# LOTP_ESP32_MCU_V3.net
KiCad netlist of a schematic drawn in EasyEDA
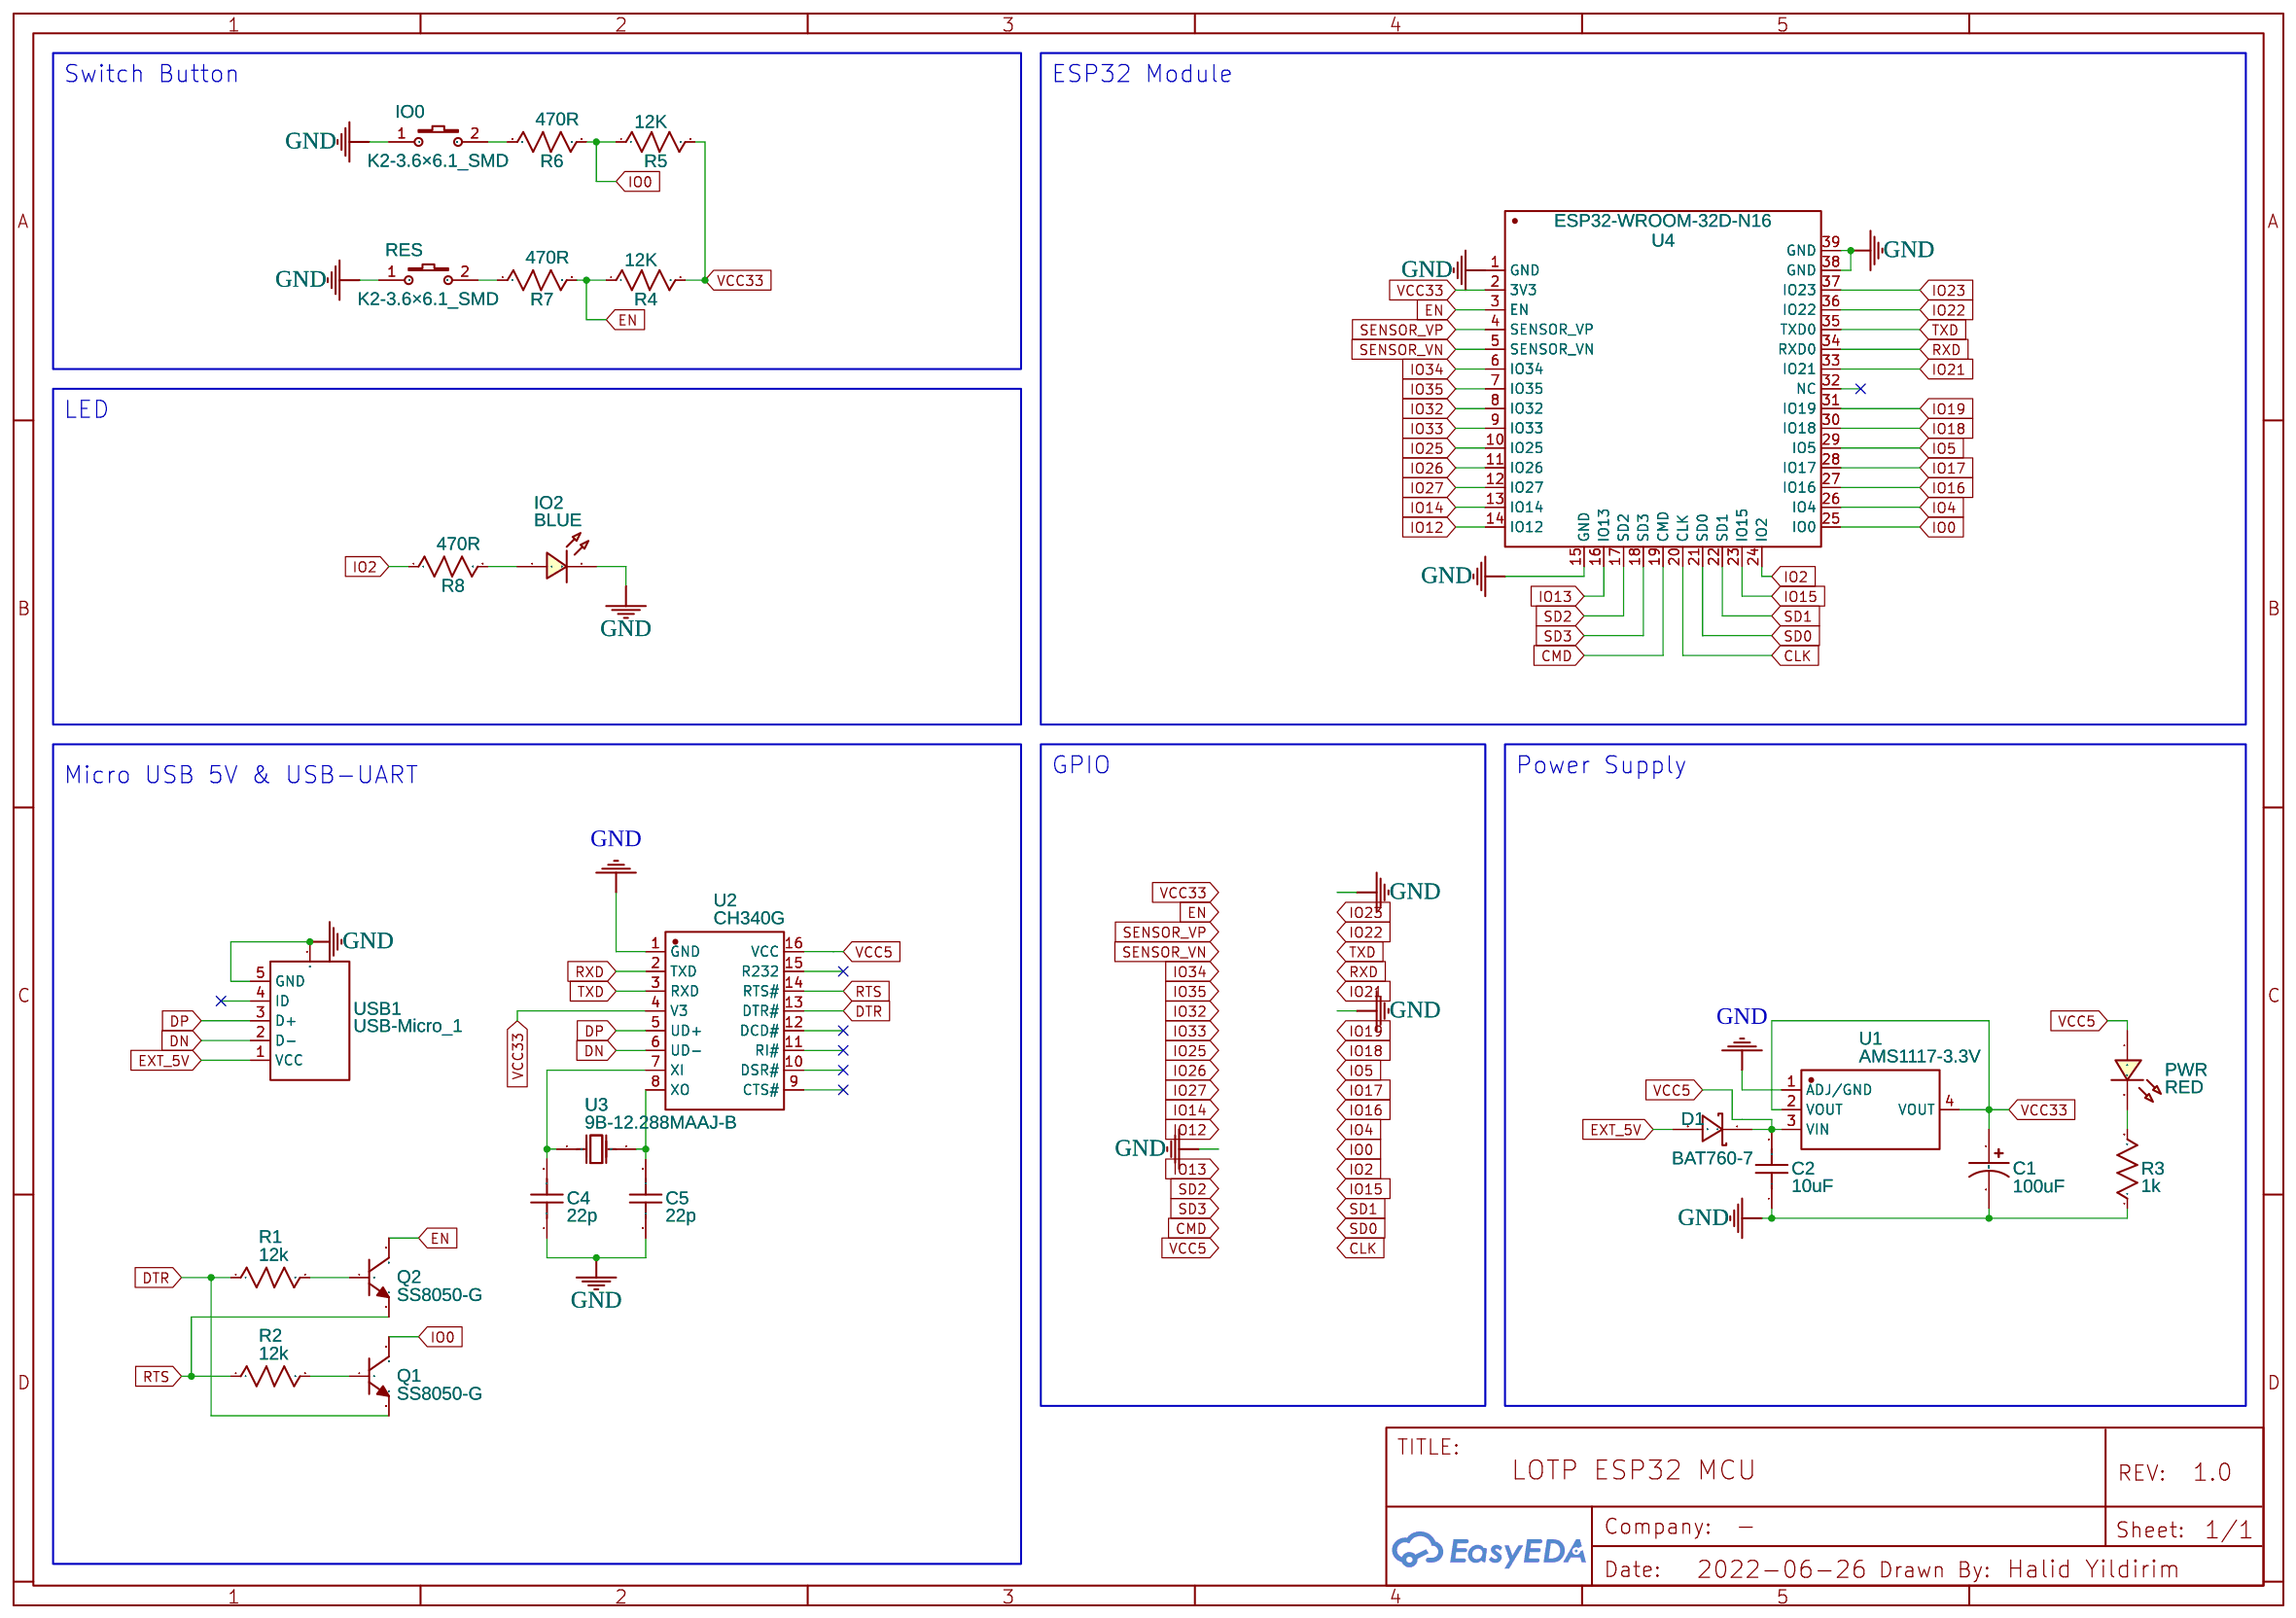
[diagram p0: schematic sheet]

(export (version "E")
  (design (tool "Eeschema 10.0.6"))
  (components
    (comp (ref "C1") (value "100uF") (libsource (lib "") (part "C_Tan_SMD_A_US")))
    (comp (ref "C2") (value "10uF") (libsource (lib "") (part "C_0603_US")))
    (comp (ref "C4") (value "22p") (libsource (lib "") (part "C_0603_US")))
    (comp (ref "C5") (value "22p") (libsource (lib "") (part "C_0603_US")))
    (comp (ref "D1")
      (value "BAT760-7")
      (fields (field (name "BOM_Supplier Part") "C124187"))
      (libsource (lib "") (part "BAT760-7"))
    )
    (comp (ref "IO0")
      (value "K2-3.6×6.1_SMD")
      (fields
        (field (name "BOM_Manufacturer Part") "K2-1107ST-A4SW-06")
        (field (name "BOM_Supplier Part") "C118141")
      )
      (libsource (lib "") (part "K2-3.6×6.1_SMD_1"))
    )
    (comp (ref "IO2")
      (value "BLUE")
      (fields
        (field (name "BOM_Manufacturer Part") "19-217/R6C-AL1M2VY/3T")
        (field (name "BOM_Supplier Part") "C72044")
      )
      (libsource (lib "") (part "LED-0603_R"))
    )
    (comp (ref "PWR")
      (value "RED")
      (fields
        (field (name "BOM_Manufacturer Part") "19-217/R6C-AL1M2VY/3T")
        (field (name "BOM_Supplier Part") "C72044")
      )
      (libsource (lib "") (part "LED-0603_R_1"))
    )
    (comp (ref "Q1")
      (value "SS8050-G")
      (fields (field (name "BOM_Supplier Part") "C164886"))
      (libsource (lib "") (part "SS8050-G"))
    )
    (comp (ref "Q2")
      (value "SS8050-G")
      (fields (field (name "BOM_Supplier Part") "C164886"))
      (libsource (lib "") (part "SS8050-G"))
    )
    (comp (ref "R1") (value "12k") (libsource (lib "") (part "R_0603_US")))
    (comp (ref "R2") (value "12k") (libsource (lib "") (part "R_0603_US")))
    (comp (ref "R3") (value "1k") (libsource (lib "") (part "R_0603_US_1")))
    (comp (ref "R4") (value "12K") (libsource (lib "") (part "R_0603_US")))
    (comp (ref "R5") (value "12K") (libsource (lib "") (part "R_0603_US")))
    (comp (ref "R6") (value "470R") (libsource (lib "") (part "R_0603_US")))
    (comp (ref "R7") (value "470R") (libsource (lib "") (part "R_0603_US")))
    (comp (ref "R8") (value "470R") (libsource (lib "") (part "R_0603_US")))
    (comp (ref "RES")
      (value "K2-3.6×6.1_SMD")
      (fields
        (field (name "BOM_Manufacturer Part") "K2-1107ST-A4SW-06")
        (field (name "BOM_Supplier Part") "C118141")
      )
      (libsource (lib "") (part "K2-3.6×6.1_SMD"))
    )
    (comp (ref "U1")
      (value "AMS1117-3.3V")
      (fields (field (name "BOM_Supplier Part") "C2688239"))
      (libsource (lib "") (part "AMS1117-3.3V"))
    )
    (comp (ref "U2")
      (value "CH340G")
      (fields (field (name "BOM_Supplier Part") "C14267"))
      (libsource (lib "") (part "CH340G"))
    )
    (comp (ref "U3")
      (value "9B-12.288MAAJ-B")
      (fields (field (name "BOM_Supplier Part") "C2636382"))
      (libsource (lib "") (part "9B-12.288MAAJ-B"))
    )
    (comp (ref "U4")
      (value "ESP32-WROOM-32D-N16")
      (fields (field (name "BOM_Supplier Part") "C2973676"))
      (libsource (lib "") (part "ESP32-WROOM-32D-N16"))
    )
    (comp (ref "USB1")
      (value "USB-Micro_1")
      (fields (field (name "BOM_Supplier Part") "C10418"))
      (libsource (lib "") (part "USB-Micro_1"))
    )
  )
  (nets
    (net (code "1") (name "CLK") (class "Default")
      (node (ref "U4") (pin "20") (pinfunction "CLK_20") (pintype "unspecified"))
    )
    (net (code "2") (name "CMD") (class "Default")
      (node (ref "U4") (pin "19") (pinfunction "CMD_19") (pintype "unspecified"))
    )
    (net (code "3") (name "DN") (class "Default")
      (node (ref "U2") (pin "6") (pinfunction "UD-_6") (pintype "unspecified"))
      (node (ref "USB1") (pin "2") (pinfunction "D-_2") (pintype "input"))
    )
    (net (code "4") (name "DP") (class "Default")
      (node (ref "U2") (pin "5") (pinfunction "UD+_5") (pintype "unspecified"))
      (node (ref "USB1") (pin "3") (pinfunction "D+_3") (pintype "input"))
    )
    (net (code "5") (name "DTR") (class "Default")
      (node (ref "Q1") (pin "2") (pinfunction "E_2") (pintype "input"))
      (node (ref "R1") (pin "1") (pinfunction "1_1") (pintype "unspecified"))
      (node (ref "U2") (pin "13") (pinfunction "DTR#_13") (pintype "unspecified"))
    )
    (net (code "6") (name "EN") (class "Default")
      (node (ref "Q2") (pin "3") (pinfunction "C_3") (pintype "input"))
      (node (ref "R4") (pin "1") (pinfunction "1_1") (pintype "unspecified"))
      (node (ref "R7") (pin "2") (pinfunction "2_2") (pintype "unspecified"))
      (node (ref "U4") (pin "3") (pinfunction "EN_3") (pintype "unspecified"))
    )
    (net (code "7") (name "EXT_5V") (class "Default")
      (node (ref "D1") (pin "2") (pinfunction "2_2") (pintype "unspecified"))
      (node (ref "USB1") (pin "1") (pinfunction "VCC_1") (pintype "input"))
    )
    (net (code "8") (name "GND") (class "Default")
      (node (ref "C1") (pin "2") (pinfunction "2_2") (pintype "unspecified"))
      (node (ref "C2") (pin "1") (pinfunction "1_1") (pintype "unspecified"))
      (node (ref "C4") (pin "1") (pinfunction "1_1") (pintype "unspecified"))
      (node (ref "C5") (pin "1") (pinfunction "1_1") (pintype "unspecified"))
      (node (ref "IO0") (pin "1") (pinfunction "1_1") (pintype "unspecified"))
      (node (ref "IO2") (pin "2") (pinfunction "2_2") (pintype "unspecified"))
      (node (ref "R3") (pin "1") (pinfunction "1_1") (pintype "unspecified"))
      (node (ref "RES") (pin "1") (pinfunction "1_1") (pintype "unspecified"))
      (node (ref "U1") (pin "1") (pinfunction "ADJ/GND_1") (pintype "unspecified"))
      (node (ref "U2") (pin "1") (pinfunction "GND_1") (pintype "unspecified"))
      (node (ref "U4") (pin "1") (pinfunction "GND_1") (pintype "unspecified"))
      (node (ref "U4") (pin "15") (pinfunction "GND_15") (pintype "unspecified"))
      (node (ref "U4") (pin "38") (pinfunction "GND_38") (pintype "unspecified"))
      (node (ref "U4") (pin "39") (pinfunction "GND_39") (pintype "unspecified"))
      (node (ref "USB1") (pin "0") (pinfunction "MTN_0") (pintype "unspecified"))
      (node (ref "USB1") (pin "5") (pinfunction "GND_5") (pintype "input"))
    )
    (net (code "9") (name "IO0") (class "Default")
      (node (ref "Q1") (pin "3") (pinfunction "C_3") (pintype "input"))
      (node (ref "R5") (pin "1") (pinfunction "1_1") (pintype "unspecified"))
      (node (ref "R6") (pin "2") (pinfunction "2_2") (pintype "unspecified"))
      (node (ref "U4") (pin "25") (pinfunction "IO0_25") (pintype "unspecified"))
    )
    (net (code "10") (name "IO2") (class "Default")
      (node (ref "R8") (pin "1") (pinfunction "1_1") (pintype "unspecified"))
      (node (ref "U4") (pin "24") (pinfunction "IO2_24") (pintype "unspecified"))
    )
    (net (code "11") (name "IO4") (class "Default")
      (node (ref "U4") (pin "26") (pinfunction "IO4_26") (pintype "unspecified"))
    )
    (net (code "12") (name "IO5") (class "Default")
      (node (ref "U4") (pin "29") (pinfunction "IO5_29") (pintype "unspecified"))
    )
    (net (code "13") (name "IO12") (class "Default")
      (node (ref "U4") (pin "14") (pinfunction "IO12_14") (pintype "unspecified"))
    )
    (net (code "14") (name "IO13") (class "Default")
      (node (ref "U4") (pin "16") (pinfunction "IO13_16") (pintype "unspecified"))
    )
    (net (code "15") (name "IO14") (class "Default")
      (node (ref "U4") (pin "13") (pinfunction "IO14_13") (pintype "unspecified"))
    )
    (net (code "16") (name "IO15") (class "Default")
      (node (ref "U4") (pin "23") (pinfunction "IO15_23") (pintype "unspecified"))
    )
    (net (code "17") (name "IO16") (class "Default")
      (node (ref "U4") (pin "27") (pinfunction "IO16_27") (pintype "unspecified"))
    )
    (net (code "18") (name "IO17") (class "Default")
      (node (ref "U4") (pin "28") (pinfunction "IO17_28") (pintype "unspecified"))
    )
    (net (code "19") (name "IO18") (class "Default")
      (node (ref "U4") (pin "30") (pinfunction "IO18_30") (pintype "unspecified"))
    )
    (net (code "20") (name "IO19") (class "Default")
      (node (ref "U4") (pin "31") (pinfunction "IO19_31") (pintype "unspecified"))
    )
    (net (code "21") (name "IO21") (class "Default")
      (node (ref "U4") (pin "33") (pinfunction "IO21_33") (pintype "unspecified"))
    )
    (net (code "22") (name "IO22") (class "Default")
      (node (ref "U4") (pin "36") (pinfunction "IO22_36") (pintype "unspecified"))
    )
    (net (code "23") (name "IO23") (class "Default")
      (node (ref "U4") (pin "37") (pinfunction "IO23_37") (pintype "unspecified"))
    )
    (net (code "24") (name "IO25") (class "Default")
      (node (ref "U4") (pin "10") (pinfunction "IO25_10") (pintype "unspecified"))
    )
    (net (code "25") (name "IO26") (class "Default")
      (node (ref "U4") (pin "11") (pinfunction "IO26_11") (pintype "unspecified"))
    )
    (net (code "26") (name "IO27") (class "Default")
      (node (ref "U4") (pin "12") (pinfunction "IO27_12") (pintype "unspecified"))
    )
    (net (code "27") (name "IO32") (class "Default")
      (node (ref "U4") (pin "8") (pinfunction "IO32_8") (pintype "unspecified"))
    )
    (net (code "28") (name "IO33") (class "Default")
      (node (ref "U4") (pin "9") (pinfunction "IO33_9") (pintype "unspecified"))
    )
    (net (code "29") (name "IO34") (class "Default")
      (node (ref "U4") (pin "6") (pinfunction "IO34_6") (pintype "unspecified"))
    )
    (net (code "30") (name "IO35") (class "Default")
      (node (ref "U4") (pin "7") (pinfunction "IO35_7") (pintype "unspecified"))
    )
    (net (code "31") (name "Net-(IO0-Pad2)") (class "Default")
      (node (ref "IO0") (pin "2") (pinfunction "2_2") (pintype "unspecified"))
      (node (ref "R6") (pin "1") (pinfunction "1_1") (pintype "unspecified"))
    )
    (net (code "32") (name "Net-(IO2-Pad1)") (class "Default")
      (node (ref "IO2") (pin "1") (pinfunction "1_1") (pintype "unspecified"))
      (node (ref "R8") (pin "2") (pinfunction "2_2") (pintype "unspecified"))
    )
    (net (code "33") (name "Net-(PWR-Pad2)") (class "Default")
      (node (ref "PWR") (pin "2") (pinfunction "2_2") (pintype "unspecified"))
      (node (ref "R3") (pin "2") (pinfunction "2_2") (pintype "unspecified"))
    )
    (net (code "34") (name "Net-(Q1-B)") (class "Default")
      (node (ref "Q1") (pin "1") (pinfunction "B_1") (pintype "input"))
      (node (ref "R2") (pin "2") (pinfunction "2_2") (pintype "unspecified"))
    )
    (net (code "35") (name "Net-(Q2-B)") (class "Default")
      (node (ref "Q2") (pin "1") (pinfunction "B_1") (pintype "input"))
      (node (ref "R1") (pin "2") (pinfunction "2_2") (pintype "unspecified"))
    )
    (net (code "36") (name "Net-(R7-Pad1)") (class "Default")
      (node (ref "R7") (pin "1") (pinfunction "1_1") (pintype "unspecified"))
      (node (ref "RES") (pin "2") (pinfunction "2_2") (pintype "unspecified"))
    )
    (net (code "37") (name "Net-(U2-XI)") (class "Default")
      (node (ref "C4") (pin "2") (pinfunction "2_2") (pintype "unspecified"))
      (node (ref "U2") (pin "7") (pinfunction "XI_7") (pintype "unspecified"))
      (node (ref "U3") (pin "1") (pinfunction "OSC1_1") (pintype "input"))
    )
    (net (code "38") (name "Net-(U2-XO)") (class "Default")
      (node (ref "C5") (pin "2") (pinfunction "2_2") (pintype "unspecified"))
      (node (ref "U2") (pin "8") (pinfunction "XO_8") (pintype "unspecified"))
      (node (ref "U3") (pin "2") (pinfunction "OSC2_2") (pintype "input"))
    )
    (net (code "39") (name "RTS") (class "Default")
      (node (ref "Q2") (pin "2") (pinfunction "E_2") (pintype "input"))
      (node (ref "R2") (pin "1") (pinfunction "1_1") (pintype "unspecified"))
      (node (ref "U2") (pin "14") (pinfunction "RTS#_14") (pintype "unspecified"))
    )
    (net (code "40") (name "RXD") (class "Default")
      (node (ref "U2") (pin "2") (pinfunction "TXD_2") (pintype "unspecified"))
      (node (ref "U4") (pin "34") (pinfunction "RXD0_34") (pintype "unspecified"))
    )
    (net (code "41") (name "SD0") (class "Default")
      (node (ref "U4") (pin "21") (pinfunction "SD0_21") (pintype "unspecified"))
    )
    (net (code "42") (name "SD1") (class "Default")
      (node (ref "U4") (pin "22") (pinfunction "SD1_22") (pintype "unspecified"))
    )
    (net (code "43") (name "SD2") (class "Default")
      (node (ref "U4") (pin "17") (pinfunction "SD2_17") (pintype "unspecified"))
    )
    (net (code "44") (name "SD3") (class "Default")
      (node (ref "U4") (pin "18") (pinfunction "SD3_18") (pintype "unspecified"))
    )
    (net (code "45") (name "SENSOR_VN") (class "Default")
      (node (ref "U4") (pin "5") (pinfunction "SENSOR_VN_5") (pintype "unspecified"))
    )
    (net (code "46") (name "SENSOR_VP") (class "Default")
      (node (ref "U4") (pin "4") (pinfunction "SENSOR_VP_4") (pintype "unspecified"))
    )
    (net (code "47") (name "TXD") (class "Default")
      (node (ref "U2") (pin "3") (pinfunction "RXD_3") (pintype "unspecified"))
      (node (ref "U4") (pin "35") (pinfunction "TXD0_35") (pintype "unspecified"))
    )
    (net (code "48") (name "VCC5") (class "Default")
      (node (ref "C2") (pin "2") (pinfunction "2_2") (pintype "unspecified"))
      (node (ref "D1") (pin "1") (pinfunction "1_1") (pintype "unspecified"))
      (node (ref "PWR") (pin "1") (pinfunction "1_1") (pintype "unspecified"))
      (node (ref "U1") (pin "3") (pinfunction "VIN_3") (pintype "unspecified"))
      (node (ref "U2") (pin "16") (pinfunction "VCC_16") (pintype "unspecified"))
    )
    (net (code "49") (name "VCC33") (class "Default")
      (node (ref "C1") (pin "1") (pinfunction "1_1") (pintype "unspecified"))
      (node (ref "R4") (pin "2") (pinfunction "2_2") (pintype "unspecified"))
      (node (ref "R5") (pin "2") (pinfunction "2_2") (pintype "unspecified"))
      (node (ref "U1") (pin "2") (pinfunction "VOUT_2") (pintype "unspecified"))
      (node (ref "U1") (pin "4") (pinfunction "VOUT_4") (pintype "unspecified"))
      (node (ref "U2") (pin "4") (pinfunction "V3_4") (pintype "unspecified"))
      (node (ref "U4") (pin "2") (pinfunction "3V3_2") (pintype "unspecified"))
    )
    (net (code "50") (name "unconnected-(U2-CTS#-Pad9)") (class "Default")
      (node (ref "U2") (pin "9") (pinfunction "CTS#_9") (pintype "unspecified+no_connect"))
    )
    (net (code "51") (name "unconnected-(U2-DCD#-Pad12)") (class "Default")
      (node (ref "U2") (pin "12") (pinfunction "DCD#_12") (pintype "unspecified+no_connect"))
    )
    (net (code "52") (name "unconnected-(U2-DSR#-Pad10)") (class "Default")
      (node (ref "U2") (pin "10") (pinfunction "DSR#_10") (pintype "unspecified+no_connect"))
    )
    (net (code "53") (name "unconnected-(U2-R232-Pad15)") (class "Default")
      (node (ref "U2") (pin "15") (pinfunction "R232_15") (pintype "unspecified+no_connect"))
    )
    (net (code "54") (name "unconnected-(U2-RI#-Pad11)") (class "Default")
      (node (ref "U2") (pin "11") (pinfunction "RI#_11") (pintype "unspecified+no_connect"))
    )
    (net (code "55") (name "unconnected-(U4-NC-Pad32)") (class "Default")
      (node (ref "U4") (pin "32") (pinfunction "NC_32") (pintype "unspecified+no_connect"))
    )
    (net (code "56") (name "unconnected-(USB1-ID-Pad4)") (class "Default")
      (node (ref "USB1") (pin "4") (pinfunction "ID_4") (pintype "input+no_connect"))
    )
  )
)
